# module.net
KiCad netlist of a schematic drawn in EAGLE
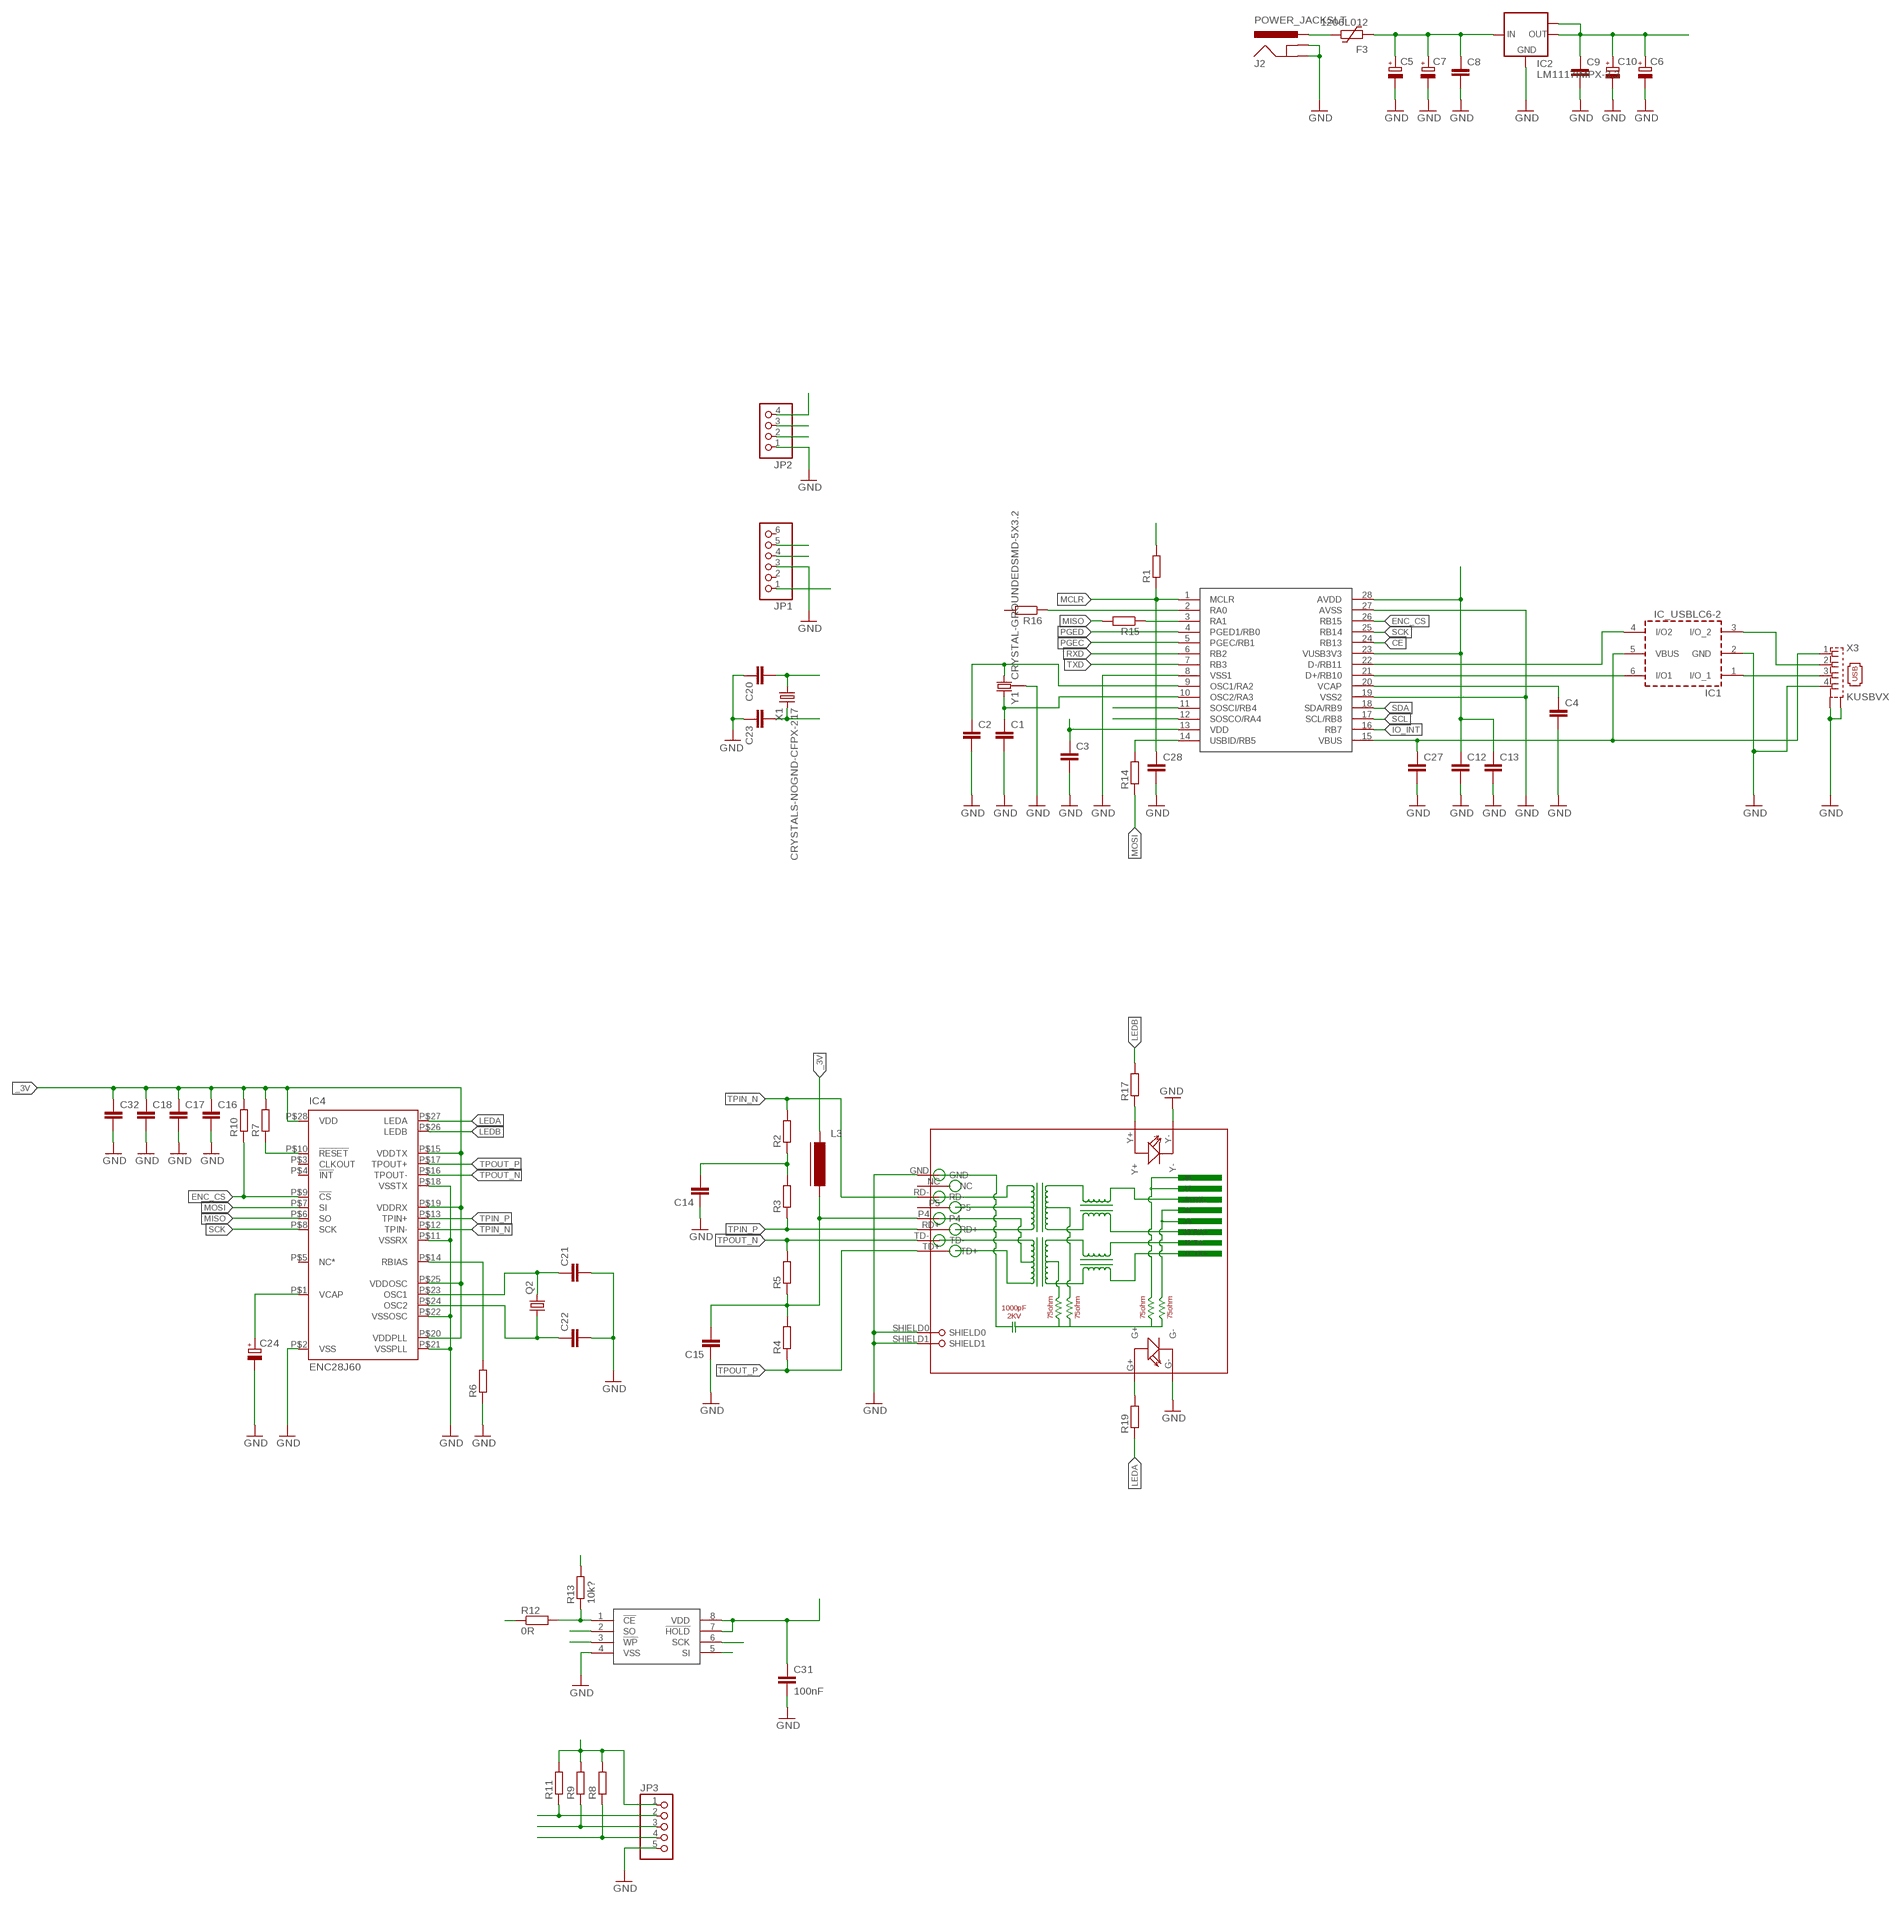
[diagram p0: schematic, sheet 1]

(export (version "E")
  (design (tool "Eeschema 10.0.6"))
  (components
    (comp (ref "C1")
      (value "C-EUC0603")
      (footprint "eagle-import:C0603")
      (libsource (lib "eagle-import") (part "C-EUC0603"))
    )
    (comp (ref "C2")
      (value "C-EUC0603")
      (footprint "eagle-import:C0603")
      (libsource (lib "eagle-import") (part "C-EUC0603"))
    )
    (comp (ref "C3")
      (value "C-EUC0402")
      (footprint "eagle-import:C0402")
      (libsource (lib "eagle-import") (part "C-EUC0402"))
    )
    (comp (ref "C4")
      (value "C-EUC0603")
      (footprint "eagle-import:C0603")
      (libsource (lib "eagle-import") (part "C-EUC0603"))
    )
    (comp (ref "C5")
      (value "CPOL-EUSMCA")
      (footprint "eagle-import:SMC_A")
      (libsource (lib "eagle-import") (part "CPOL-EUSMCA"))
    )
    (comp (ref "C6")
      (value "CPOL-EUSMCA")
      (footprint "eagle-import:SMC_A")
      (libsource (lib "eagle-import") (part "CPOL-EUSMCA"))
    )
    (comp (ref "C7")
      (value "CPOL-EUSMCC")
      (footprint "eagle-import:SMC_C")
      (libsource (lib "eagle-import") (part "CPOL-EUSMCC"))
    )
    (comp (ref "C8")
      (value "C-EUC0603")
      (footprint "eagle-import:C0603")
      (libsource (lib "eagle-import") (part "C-EUC0603"))
    )
    (comp (ref "C9")
      (value "C-EUC0603")
      (footprint "eagle-import:C0603")
      (libsource (lib "eagle-import") (part "C-EUC0603"))
    )
    (comp (ref "C10")
      (value "CPOL-EUSMCB")
      (footprint "eagle-import:SMC_B")
      (libsource (lib "eagle-import") (part "CPOL-EUSMCB"))
    )
    (comp (ref "C12")
      (value "C-EUC0402")
      (footprint "eagle-import:C0402")
      (libsource (lib "eagle-import") (part "C-EUC0402"))
    )
    (comp (ref "C13")
      (value "C-EUC0603")
      (footprint "eagle-import:C0603")
      (libsource (lib "eagle-import") (part "C-EUC0603"))
    )
    (comp (ref "C14")
      (value "C-EUC0603")
      (footprint "eagle-import:C0603")
      (libsource (lib "eagle-import") (part "C-EUC0603"))
    )
    (comp (ref "C15")
      (value "C-EUC0603")
      (footprint "eagle-import:C0603")
      (libsource (lib "eagle-import") (part "C-EUC0603"))
    )
    (comp (ref "C16")
      (value "C-EUC0402")
      (footprint "eagle-import:C0402")
      (libsource (lib "eagle-import") (part "C-EUC0402"))
    )
    (comp (ref "C17")
      (value "C-EUC0603")
      (footprint "eagle-import:C0603")
      (libsource (lib "eagle-import") (part "C-EUC0603"))
    )
    (comp (ref "C18")
      (value "C-EUC0603")
      (footprint "eagle-import:C0603")
      (libsource (lib "eagle-import") (part "C-EUC0603"))
    )
    (comp (ref "C20")
      (value "C-EUC0603")
      (footprint "eagle-import:C0603")
      (libsource (lib "eagle-import") (part "C-EUC0603"))
    )
    (comp (ref "C21")
      (value "C-EUC0603")
      (footprint "eagle-import:C0603")
      (libsource (lib "eagle-import") (part "C-EUC0603"))
    )
    (comp (ref "C22")
      (value "C-EUC0603")
      (footprint "eagle-import:C0603")
      (libsource (lib "eagle-import") (part "C-EUC0603"))
    )
    (comp (ref "C23")
      (value "C-EUC0603")
      (footprint "eagle-import:C0603")
      (libsource (lib "eagle-import") (part "C-EUC0603"))
    )
    (comp (ref "C24")
      (value "CPOL-EUSMCA")
      (footprint "eagle-import:SMC_A")
      (libsource (lib "eagle-import") (part "CPOL-EUSMCA"))
    )
    (comp (ref "C27")
      (value "C-EUC0603")
      (footprint "eagle-import:C0603")
      (libsource (lib "eagle-import") (part "C-EUC0603"))
    )
    (comp (ref "C28")
      (value "C-EUC0603")
      (footprint "eagle-import:C0603")
      (libsource (lib "eagle-import") (part "C-EUC0603"))
    )
    (comp (ref "C31")
      (value "100nF")
      (footprint "eagle-import:C0603")
      (libsource (lib "eagle-import") (part "C-EUC0603"))
    )
    (comp (ref "C32")
      (value "C-EUC0402")
      (footprint "eagle-import:C0402")
      (libsource (lib "eagle-import") (part "C-EUC0402"))
    )
    (comp (ref "F3")
      (value "1206L012")
      (footprint "eagle-import:1206L")
      (fields (field (name "MF") "Littelfuse"))
      (libsource (lib "eagle-import") (part "?1206L012"))
    )
    (comp (ref "IC1")
      (value "IC_USBLC6-2")
      (footprint "eagle-import:SOT-23-6L")
      (libsource (lib "eagle-import") (part "IC_USBLC6-2"))
    )
    (comp (ref "IC2")
      (value "LM1117IMPX-3.3")
      (footprint "eagle-import:SOT223")
      (libsource (lib "eagle-import") (part "LM1117IMPX-3.3"))
    )
    (comp (ref "IC4")
      (value "ENC28J60")
      (footprint "eagle-import:TSSOP28W")
      (libsource (lib "eagle-import") (part "ENC28J60"))
    )
    (comp (ref "J2")
      (value "POWER_JACKSLT")
      (footprint "eagle-import:POWER_JACK_SLOT")
      (libsource (lib "eagle-import") (part "POWER_JACKSLT"))
    )
    (comp (ref "JP1")
      (value "PINHD-1X6")
      (footprint "eagle-import:1X06")
      (libsource (lib "eagle-import") (part "PINHD-1X6"))
    )
    (comp (ref "JP2")
      (value "PINHD-1X4")
      (footprint "eagle-import:1X04")
      (libsource (lib "eagle-import") (part "PINHD-1X4"))
    )
    (comp (ref "JP3")
      (value "PINHD-1X5")
      (footprint "eagle-import:1X05")
      (libsource (lib "eagle-import") (part "PINHD-1X5"))
    )
    (comp (ref "L3")
      (value "FERRITE-0805")
      (footprint "eagle-import:FB805")
      (libsource (lib "eagle-import") (part "FERRITE-0805"))
    )
    (comp (ref "Q2")
      (value "CRYSTALHC49S")
      (footprint "eagle-import:HC49_S")
      (libsource (lib "eagle-import") (part "CRYSTALHC49S"))
    )
    (comp (ref "R1")
      (value "R-EU_R0603")
      (footprint "eagle-import:R0603")
      (libsource (lib "eagle-import") (part "R-EU_R0603"))
    )
    (comp (ref "R2")
      (value "R-EU_R0603")
      (footprint "eagle-import:R0603")
      (libsource (lib "eagle-import") (part "R-EU_R0603"))
    )
    (comp (ref "R3")
      (value "R-EU_R0603")
      (footprint "eagle-import:R0603")
      (libsource (lib "eagle-import") (part "R-EU_R0603"))
    )
    (comp (ref "R4")
      (value "R-EU_R0603")
      (footprint "eagle-import:R0603")
      (libsource (lib "eagle-import") (part "R-EU_R0603"))
    )
    (comp (ref "R5")
      (value "R-EU_R0603")
      (footprint "eagle-import:R0603")
      (libsource (lib "eagle-import") (part "R-EU_R0603"))
    )
    (comp (ref "R6")
      (value "R-EU_R0805")
      (footprint "eagle-import:R0805")
      (libsource (lib "eagle-import") (part "R-EU_R0805"))
    )
    (comp (ref "R7")
      (value "R-EU_R0603")
      (footprint "eagle-import:R0603")
      (libsource (lib "eagle-import") (part "R-EU_R0603"))
    )
    (comp (ref "R8")
      (value "R-EU_R0402")
      (footprint "eagle-import:R0402")
      (libsource (lib "eagle-import") (part "R-EU_R0402"))
    )
    (comp (ref "R9")
      (value "R-EU_R0402")
      (footprint "eagle-import:R0402")
      (libsource (lib "eagle-import") (part "R-EU_R0402"))
    )
    (comp (ref "R10")
      (value "R-EU_R0603")
      (footprint "eagle-import:R0603")
      (libsource (lib "eagle-import") (part "R-EU_R0603"))
    )
    (comp (ref "R11")
      (value "R-EU_R0402")
      (footprint "eagle-import:R0402")
      (libsource (lib "eagle-import") (part "R-EU_R0402"))
    )
    (comp (ref "R12")
      (value "0R")
      (footprint "eagle-import:R0603")
      (libsource (lib "eagle-import") (part "R-EU_R0603"))
    )
    (comp (ref "R13")
      (value "10k?")
      (footprint "eagle-import:R0603")
      (libsource (lib "eagle-import") (part "R-EU_R0603"))
    )
    (comp (ref "R14")
      (value "R-EU_R0603")
      (footprint "eagle-import:R0603")
      (libsource (lib "eagle-import") (part "R-EU_R0603"))
    )
    (comp (ref "R15")
      (value "R-EU_R0603")
      (footprint "eagle-import:R0603")
      (libsource (lib "eagle-import") (part "R-EU_R0603"))
    )
    (comp (ref "R16")
      (value "R-EU_R1206")
      (footprint "eagle-import:R1206")
      (libsource (lib "eagle-import") (part "R-EU_R1206"))
    )
    (comp (ref "R17")
      (value "R-EU_R1206")
      (footprint "eagle-import:R1206")
      (libsource (lib "eagle-import") (part "R-EU_R1206"))
    )
    (comp (ref "R19")
      (value "R-EU_R1206")
      (footprint "eagle-import:R1206")
      (libsource (lib "eagle-import") (part "R-EU_R1206"))
    )
    (comp (ref "RJ1")
      (value "HR911105A")
      (footprint "eagle-import:HR911105A")
      (libsource (lib "eagle-import") (part "HR911105A"))
    )
    (comp (ref "U$1")
      (value "PIC32MX250F128B2")
      (footprint "eagle-import:SSOP28")
      (libsource (lib "eagle-import") (part "PIC32MX250F128B2"))
    )
    (comp (ref "U$2")
      (value "SST25VF016BSO8M")
      (footprint "eagle-import:SO-08M")
      (libsource (lib "eagle-import") (part "SST25VF016BSO8M"))
    )
    (comp (ref "X1")
      (value "CRYSTALS-NOGND-CFPX-217")
      (footprint "eagle-import:3.2X1.5-2-PAD")
      (libsource (lib "eagle-import") (part "CRYSTALS-NOGND-CFPX-217"))
    )
    (comp (ref "X3")
      (value "KUSBVX")
      (footprint "eagle-import:KUSBVX")
      (libsource (lib "eagle-import") (part "KUSBVX"))
    )
    (comp (ref "Y1")
      (value "CRYSTAL-GROUNDEDSMD-5X3.2")
      (footprint "eagle-import:CRYSTAL-SMD-5X3.2-4PAD")
      (libsource (lib "eagle-import") (part "CRYSTAL-GROUNDEDSMD-5X3.2"))
    )
  )
  (nets
    (net (code "1") (name "/SOSCI") (class "Default")
      (node (ref "C20") (pin "2") (pinfunction "2_2") (pintype "passive"))
      (node (ref "U$1") (pin "11") (pinfunction "SOSCI/RB4_11") (pintype "bidirectional"))
      (node (ref "X1") (pin "1") (pinfunction "1_1") (pintype "passive"))
    )
    (net (code "2") (name "/SOSCO") (class "Default")
      (node (ref "C23") (pin "2") (pinfunction "2_2") (pintype "passive"))
      (node (ref "U$1") (pin "12") (pinfunction "SOSCO/RA4_12") (pintype "bidirectional"))
      (node (ref "X1") (pin "2") (pinfunction "2_2") (pintype "passive"))
    )
    (net (code "3") (name "/VBUS") (class "Default")
      (node (ref "C27") (pin "1") (pinfunction "1_1") (pintype "passive"))
      (node (ref "C5") (pin "+") (pinfunction "+_+") (pintype "passive"))
      (node (ref "C7") (pin "+") (pinfunction "+_+") (pintype "passive"))
      (node (ref "C8") (pin "1") (pinfunction "1_1") (pintype "passive"))
      (node (ref "F3") (pin "2") (pinfunction "2_2") (pintype "passive"))
      (node (ref "IC1") (pin "5") (pinfunction "VBUS_5") (pintype "bidirectional"))
      (node (ref "IC2") (pin "3") (pinfunction "IN_3") (pintype "input"))
      (node (ref "U$1") (pin "15") (pinfunction "VBUS_15") (pintype "bidirectional"))
      (node (ref "X3") (pin "1") (pinfunction "1_1") (pintype "passive"))
    )
    (net (code "4") (name "CE") (class "Default")
      (node (ref "R12") (pin "1") (pinfunction "1_1") (pintype "passive"))
      (node (ref "U$1") (pin "24") (pinfunction "RB13_24") (pintype "bidirectional"))
    )
    (net (code "5") (name "ENC_CS") (class "Default")
      (node (ref "IC4") (pin "P$9") (pinfunction "~{CS}_P$9") (pintype "input"))
      (node (ref "R10") (pin "1") (pinfunction "1_1") (pintype "passive"))
      (node (ref "U$1") (pin "26") (pinfunction "RB15_26") (pintype "bidirectional"))
    )
    (net (code "6") (name "GND") (class "Default")
      (node (ref "C1") (pin "2") (pinfunction "2_2") (pintype "passive"))
      (node (ref "C10") (pin "-") (pinfunction "-_-") (pintype "passive"))
      (node (ref "C12") (pin "2") (pinfunction "2_2") (pintype "passive"))
      (node (ref "C13") (pin "2") (pinfunction "2_2") (pintype "passive"))
      (node (ref "C14") (pin "1") (pinfunction "1_1") (pintype "passive"))
      (node (ref "C15") (pin "1") (pinfunction "1_1") (pintype "passive"))
      (node (ref "C16") (pin "2") (pinfunction "2_2") (pintype "passive"))
      (node (ref "C17") (pin "2") (pinfunction "2_2") (pintype "passive"))
      (node (ref "C18") (pin "2") (pinfunction "2_2") (pintype "passive"))
      (node (ref "C2") (pin "2") (pinfunction "2_2") (pintype "passive"))
      (node (ref "C20") (pin "1") (pinfunction "1_1") (pintype "passive"))
      (node (ref "C21") (pin "2") (pinfunction "2_2") (pintype "passive"))
      (node (ref "C22") (pin "2") (pinfunction "2_2") (pintype "passive"))
      (node (ref "C23") (pin "1") (pinfunction "1_1") (pintype "passive"))
      (node (ref "C24") (pin "-") (pinfunction "-_-") (pintype "passive"))
      (node (ref "C27") (pin "2") (pinfunction "2_2") (pintype "passive"))
      (node (ref "C28") (pin "2") (pinfunction "2_2") (pintype "passive"))
      (node (ref "C3") (pin "2") (pinfunction "2_2") (pintype "passive"))
      (node (ref "C31") (pin "2") (pinfunction "2_2") (pintype "passive"))
      (node (ref "C32") (pin "2") (pinfunction "2_2") (pintype "passive"))
      (node (ref "C4") (pin "2") (pinfunction "2_2") (pintype "passive"))
      (node (ref "C5") (pin "-") (pinfunction "-_-") (pintype "passive"))
      (node (ref "C6") (pin "-") (pinfunction "-_-") (pintype "passive"))
      (node (ref "C7") (pin "-") (pinfunction "-_-") (pintype "passive"))
      (node (ref "C8") (pin "2") (pinfunction "2_2") (pintype "passive"))
      (node (ref "C9") (pin "2") (pinfunction "2_2") (pintype "passive"))
      (node (ref "IC1") (pin "2") (pinfunction "GND_2") (pintype "bidirectional"))
      (node (ref "IC2") (pin "1") (pinfunction "GND_1") (pintype "input"))
      (node (ref "IC4") (pin "P$11") (pinfunction "VSSRX_P$11") (pintype "input"))
      (node (ref "IC4") (pin "P$18") (pinfunction "VSSTX_P$18") (pintype "input"))
      (node (ref "IC4") (pin "P$2") (pinfunction "VSS_P$2") (pintype "input"))
      (node (ref "IC4") (pin "P$21") (pinfunction "VSSPLL_P$21") (pintype "input"))
      (node (ref "IC4") (pin "P$22") (pinfunction "VSSOSC_P$22") (pintype "input"))
      (node (ref "J2") (pin "GND@1") (pinfunction "GNDBREAK_GND@1") (pintype "bidirectional"))
      (node (ref "J2") (pin "GND@2") (pinfunction "GND_GND@2") (pintype "bidirectional"))
      (node (ref "JP1") (pin "3") (pinfunction "3_3") (pintype "passive"))
      (node (ref "JP2") (pin "1") (pinfunction "1_1") (pintype "passive"))
      (node (ref "JP3") (pin "5") (pinfunction "5_5") (pintype "passive"))
      (node (ref "R6") (pin "1") (pinfunction "1_1") (pintype "passive"))
      (node (ref "RJ1") (pin "G-") (pinfunction "G-_G-") (pintype "bidirectional"))
      (node (ref "RJ1") (pin "GND") (pinfunction "GND_GND") (pintype "bidirectional"))
      (node (ref "RJ1") (pin "SHIELD0") (pinfunction "SHIELD0_SHIELD0") (pintype "bidirectional"))
      (node (ref "RJ1") (pin "SHIELD1") (pinfunction "SHIELD1_SHIELD1") (pintype "bidirectional"))
      (node (ref "RJ1") (pin "Y-") (pinfunction "Y-_Y-") (pintype "bidirectional"))
      (node (ref "U$1") (pin "19") (pinfunction "VSS2_19") (pintype "bidirectional"))
      (node (ref "U$1") (pin "27") (pinfunction "AVSS_27") (pintype "bidirectional"))
      (node (ref "U$1") (pin "8") (pinfunction "VSS1_8") (pintype "bidirectional"))
      (node (ref "U$2") (pin "4") (pinfunction "VSS_4") (pintype "bidirectional"))
      (node (ref "X3") (pin "4") (pinfunction "4_4") (pintype "passive"))
      (node (ref "X3") (pin "M1") (pinfunction "S1_M1") (pintype "passive"))
      (node (ref "X3") (pin "M2") (pinfunction "S2_M2") (pintype "passive"))
      (node (ref "Y1") (pin "2") (pinfunction "3_2") (pintype "passive"))
      (node (ref "Y1") (pin "4") (pinfunction "3_4") (pintype "passive"))
    )
    (net (code "7") (name "IO_INT") (class "Default")
      (node (ref "JP3") (pin "4") (pinfunction "4_4") (pintype "passive"))
      (node (ref "R8") (pin "1") (pinfunction "1_1") (pintype "passive"))
      (node (ref "U$1") (pin "16") (pinfunction "RB7_16") (pintype "bidirectional"))
    )
    (net (code "8") (name "LEDA") (class "Default")
      (node (ref "IC4") (pin "P$27") (pinfunction "LEDA_P$27") (pintype "output"))
      (node (ref "R19") (pin "1") (pinfunction "1_1") (pintype "passive"))
    )
    (net (code "9") (name "LEDB") (class "Default")
      (node (ref "IC4") (pin "P$26") (pinfunction "LEDB_P$26") (pintype "output"))
      (node (ref "R17") (pin "2") (pinfunction "2_2") (pintype "passive"))
    )
    (net (code "10") (name "MCLR") (class "Default")
      (node (ref "C28") (pin "1") (pinfunction "1_1") (pintype "passive"))
      (node (ref "JP1") (pin "1") (pinfunction "1_1") (pintype "passive"))
      (node (ref "R1") (pin "1") (pinfunction "1_1") (pintype "passive"))
      (node (ref "U$1") (pin "1") (pinfunction "MCLR_1") (pintype "bidirectional"))
    )
    (net (code "11") (name "MISO") (class "Default")
      (node (ref "IC4") (pin "P$6") (pinfunction "SO_P$6") (pintype "output"))
      (node (ref "R15") (pin "2") (pinfunction "2_2") (pintype "passive"))
      (node (ref "U$2") (pin "2") (pinfunction "SO_2") (pintype "bidirectional"))
    )
    (net (code "12") (name "MOSI") (class "Default")
      (node (ref "IC4") (pin "P$7") (pinfunction "SI_P$7") (pintype "input"))
      (node (ref "R14") (pin "1") (pinfunction "1_1") (pintype "passive"))
      (node (ref "U$2") (pin "5") (pinfunction "SI_5") (pintype "bidirectional"))
    )
    (net (code "13") (name "Net-(C14-Pad2)") (class "Default")
      (node (ref "C14") (pin "2") (pinfunction "2_2") (pintype "passive"))
      (node (ref "R2") (pin "1") (pinfunction "1_1") (pintype "passive"))
      (node (ref "R3") (pin "2") (pinfunction "2_2") (pintype "passive"))
    )
    (net (code "14") (name "Net-(C15-Pad2)") (class "Default")
      (node (ref "C15") (pin "2") (pinfunction "2_2") (pintype "passive"))
      (node (ref "L3") (pin "2") (pinfunction "2_2") (pintype "passive"))
      (node (ref "R4") (pin "2") (pinfunction "2_2") (pintype "passive"))
      (node (ref "R5") (pin "1") (pinfunction "1_1") (pintype "passive"))
      (node (ref "RJ1") (pin "P4") (pinfunction "P4_P4") (pintype "bidirectional"))
    )
    (net (code "15") (name "Net-(F3-Pad1)") (class "Default")
      (node (ref "F3") (pin "1") (pinfunction "1_1") (pintype "passive"))
      (node (ref "J2") (pin "PWR") (pinfunction "PWR_PWR") (pintype "bidirectional"))
    )
    (net (code "16") (name "Net-(IC1-I{slash}O1)") (class "Default")
      (node (ref "IC1") (pin "6") (pinfunction "I/O1_6") (pintype "bidirectional"))
      (node (ref "U$1") (pin "21") (pinfunction "D+/RB10_21") (pintype "bidirectional"))
    )
    (net (code "17") (name "Net-(IC1-I{slash}O2)") (class "Default")
      (node (ref "IC1") (pin "4") (pinfunction "I/O2_4") (pintype "bidirectional"))
      (node (ref "U$1") (pin "22") (pinfunction "D-/RB11_22") (pintype "bidirectional"))
    )
    (net (code "18") (name "Net-(IC1-I{slash}O_1)") (class "Default")
      (node (ref "IC1") (pin "1") (pinfunction "I/O_1_1") (pintype "bidirectional"))
      (node (ref "X3") (pin "3") (pinfunction "3_3") (pintype "passive"))
    )
    (net (code "19") (name "Net-(IC1-I{slash}O_2)") (class "Default")
      (node (ref "IC1") (pin "3") (pinfunction "I/O_2_3") (pintype "bidirectional"))
      (node (ref "X3") (pin "2") (pinfunction "2_2") (pintype "passive"))
    )
    (net (code "20") (name "Net-(IC4-OSC1)") (class "Default")
      (node (ref "C21") (pin "1") (pinfunction "1_1") (pintype "passive"))
      (node (ref "IC4") (pin "P$23") (pinfunction "OSC1_P$23") (pintype "input"))
      (node (ref "Q2") (pin "2") (pinfunction "2_2") (pintype "passive"))
    )
    (net (code "21") (name "Net-(IC4-OSC2)") (class "Default")
      (node (ref "C22") (pin "1") (pinfunction "1_1") (pintype "passive"))
      (node (ref "IC4") (pin "P$24") (pinfunction "OSC2_P$24") (pintype "output"))
      (node (ref "Q2") (pin "1") (pinfunction "1_1") (pintype "passive"))
    )
    (net (code "22") (name "Net-(IC4-RBIAS)") (class "Default")
      (node (ref "IC4") (pin "P$14") (pinfunction "RBIAS_P$14") (pintype "input"))
      (node (ref "R6") (pin "2") (pinfunction "2_2") (pintype "passive"))
    )
    (net (code "23") (name "Net-(IC4-VCAP)") (class "Default")
      (node (ref "C24") (pin "+") (pinfunction "+_+") (pintype "passive"))
      (node (ref "IC4") (pin "P$1") (pinfunction "VCAP_P$1") (pintype "input"))
    )
    (net (code "24") (name "Net-(IC4-~{RESET})") (class "Default")
      (node (ref "IC4") (pin "P$10") (pinfunction "~{RESET}_P$10") (pintype "input"))
      (node (ref "R7") (pin "1") (pinfunction "1_1") (pintype "passive"))
    )
    (net (code "25") (name "Net-(R17-Pad1)") (class "Default")
      (node (ref "R17") (pin "1") (pinfunction "1_1") (pintype "passive"))
      (node (ref "RJ1") (pin "Y+") (pinfunction "Y+_Y+") (pintype "bidirectional"))
    )
    (net (code "26") (name "Net-(R19-Pad2)") (class "Default")
      (node (ref "R19") (pin "2") (pinfunction "2_2") (pintype "passive"))
      (node (ref "RJ1") (pin "G+") (pinfunction "G+_G+") (pintype "bidirectional"))
    )
    (net (code "27") (name "Net-(U$1-OSC1{slash}RA2)") (class "Default")
      (node (ref "C2") (pin "1") (pinfunction "1_1") (pintype "passive"))
      (node (ref "U$1") (pin "9") (pinfunction "OSC1/RA2_9") (pintype "bidirectional"))
      (node (ref "Y1") (pin "1") (pinfunction "2_1") (pintype "passive"))
    )
    (net (code "28") (name "Net-(U$1-OSC2{slash}RA3)") (class "Default")
      (node (ref "C1") (pin "1") (pinfunction "1_1") (pintype "passive"))
      (node (ref "U$1") (pin "10") (pinfunction "OSC2/RA3_10") (pintype "bidirectional"))
      (node (ref "Y1") (pin "3") (pinfunction "1_3") (pintype "passive"))
    )
    (net (code "29") (name "Net-(U$1-RA0)") (class "Default")
      (node (ref "R16") (pin "1") (pinfunction "1_1") (pintype "passive"))
      (node (ref "U$1") (pin "2") (pinfunction "RA0_2") (pintype "bidirectional"))
    )
    (net (code "30") (name "Net-(U$1-RA1)") (class "Default")
      (node (ref "R15") (pin "1") (pinfunction "1_1") (pintype "passive"))
      (node (ref "U$1") (pin "3") (pinfunction "RA1_3") (pintype "bidirectional"))
    )
    (net (code "31") (name "Net-(U$1-USBID{slash}RB5)") (class "Default")
      (node (ref "R14") (pin "2") (pinfunction "2_2") (pintype "passive"))
      (node (ref "U$1") (pin "14") (pinfunction "USBID/RB5_14") (pintype "bidirectional"))
    )
    (net (code "32") (name "Net-(U$1-VCAP)") (class "Default")
      (node (ref "C4") (pin "1") (pinfunction "1_1") (pintype "passive"))
      (node (ref "U$1") (pin "20") (pinfunction "VCAP_20") (pintype "bidirectional"))
    )
    (net (code "33") (name "Net-(U$2-~{CE})") (class "Default")
      (node (ref "R12") (pin "2") (pinfunction "2_2") (pintype "passive"))
      (node (ref "R13") (pin "1") (pinfunction "1_1") (pintype "passive"))
      (node (ref "U$2") (pin "1") (pinfunction "~{CE}_1") (pintype "bidirectional"))
    )
    (net (code "34") (name "PGEC") (class "Default")
      (node (ref "JP1") (pin "5") (pinfunction "5_5") (pintype "passive"))
      (node (ref "U$1") (pin "5") (pinfunction "PGEC/RB1_5") (pintype "bidirectional"))
    )
    (net (code "35") (name "PGED") (class "Default")
      (node (ref "JP1") (pin "4") (pinfunction "4_4") (pintype "passive"))
      (node (ref "U$1") (pin "4") (pinfunction "PGED1/RB0_4") (pintype "bidirectional"))
    )
    (net (code "36") (name "RXD") (class "Default")
      (node (ref "JP2") (pin "3") (pinfunction "3_3") (pintype "passive"))
      (node (ref "U$1") (pin "6") (pinfunction "RB2_6") (pintype "bidirectional"))
    )
    (net (code "37") (name "SCK") (class "Default")
      (node (ref "IC4") (pin "P$8") (pinfunction "SCK_P$8") (pintype "input"))
      (node (ref "U$1") (pin "25") (pinfunction "RB14_25") (pintype "bidirectional"))
      (node (ref "U$2") (pin "6") (pinfunction "SCK_6") (pintype "bidirectional"))
    )
    (net (code "38") (name "SCL") (class "Default")
      (node (ref "JP3") (pin "3") (pinfunction "3_3") (pintype "passive"))
      (node (ref "R9") (pin "1") (pinfunction "1_1") (pintype "passive"))
      (node (ref "U$1") (pin "17") (pinfunction "SCL/RB8_17") (pintype "bidirectional"))
    )
    (net (code "39") (name "SDA") (class "Default")
      (node (ref "JP3") (pin "2") (pinfunction "2_2") (pintype "passive"))
      (node (ref "R11") (pin "1") (pinfunction "1_1") (pintype "passive"))
      (node (ref "U$1") (pin "18") (pinfunction "SDA/RB9_18") (pintype "bidirectional"))
    )
    (net (code "40") (name "TPIN_N") (class "Default")
      (node (ref "IC4") (pin "P$12") (pinfunction "TPIN-_P$12") (pintype "input"))
      (node (ref "R2") (pin "2") (pinfunction "2_2") (pintype "passive"))
      (node (ref "RJ1") (pin "RD-") (pinfunction "RD-_RD-") (pintype "bidirectional"))
    )
    (net (code "41") (name "TPIN_P") (class "Default")
      (node (ref "IC4") (pin "P$13") (pinfunction "TPIN+_P$13") (pintype "input"))
      (node (ref "R3") (pin "1") (pinfunction "1_1") (pintype "passive"))
      (node (ref "RJ1") (pin "RD+") (pinfunction "RD+_RD+") (pintype "bidirectional"))
    )
    (net (code "42") (name "TPOUT_N") (class "Default")
      (node (ref "IC4") (pin "P$16") (pinfunction "TPOUT-_P$16") (pintype "output"))
      (node (ref "R5") (pin "2") (pinfunction "2_2") (pintype "passive"))
      (node (ref "RJ1") (pin "TD-") (pinfunction "TD-_TD-") (pintype "bidirectional"))
    )
    (net (code "43") (name "TPOUT_P") (class "Default")
      (node (ref "IC4") (pin "P$17") (pinfunction "TPOUT+_P$17") (pintype "output"))
      (node (ref "R4") (pin "1") (pinfunction "1_1") (pintype "passive"))
      (node (ref "RJ1") (pin "TD+") (pinfunction "TD+_TD+") (pintype "bidirectional"))
    )
    (net (code "44") (name "TXD") (class "Default")
      (node (ref "JP2") (pin "2") (pinfunction "2_2") (pintype "passive"))
      (node (ref "U$1") (pin "7") (pinfunction "RB3_7") (pintype "bidirectional"))
    )
    (net (code "45") (name "_3V") (class "Default")
      (node (ref "C10") (pin "+") (pinfunction "+_+") (pintype "passive"))
      (node (ref "C12") (pin "1") (pinfunction "1_1") (pintype "passive"))
      (node (ref "C13") (pin "1") (pinfunction "1_1") (pintype "passive"))
      (node (ref "C16") (pin "1") (pinfunction "1_1") (pintype "passive"))
      (node (ref "C17") (pin "1") (pinfunction "1_1") (pintype "passive"))
      (node (ref "C18") (pin "1") (pinfunction "1_1") (pintype "passive"))
      (node (ref "C3") (pin "1") (pinfunction "1_1") (pintype "passive"))
      (node (ref "C31") (pin "1") (pinfunction "1_1") (pintype "passive"))
      (node (ref "C32") (pin "1") (pinfunction "1_1") (pintype "passive"))
      (node (ref "C6") (pin "+") (pinfunction "+_+") (pintype "passive"))
      (node (ref "C9") (pin "1") (pinfunction "1_1") (pintype "passive"))
      (node (ref "IC2") (pin "2") (pinfunction "OUT_2") (pintype "passive"))
      (node (ref "IC2") (pin "TAB") (pinfunction "OUT1_TAB") (pintype "passive"))
      (node (ref "IC4") (pin "P$15") (pinfunction "VDDTX_P$15") (pintype "input"))
      (node (ref "IC4") (pin "P$19") (pinfunction "VDDRX_P$19") (pintype "input"))
      (node (ref "IC4") (pin "P$20") (pinfunction "VDDPLL_P$20") (pintype "input"))
      (node (ref "IC4") (pin "P$25") (pinfunction "VDDOSC_P$25") (pintype "input"))
      (node (ref "IC4") (pin "P$28") (pinfunction "VDD_P$28") (pintype "input"))
      (node (ref "JP2") (pin "4") (pinfunction "4_4") (pintype "passive"))
      (node (ref "JP3") (pin "1") (pinfunction "1_1") (pintype "passive"))
      (node (ref "L3") (pin "1") (pinfunction "1_1") (pintype "passive"))
      (node (ref "R1") (pin "2") (pinfunction "2_2") (pintype "passive"))
      (node (ref "R10") (pin "2") (pinfunction "2_2") (pintype "passive"))
      (node (ref "R11") (pin "2") (pinfunction "2_2") (pintype "passive"))
      (node (ref "R13") (pin "2") (pinfunction "2_2") (pintype "passive"))
      (node (ref "R7") (pin "2") (pinfunction "2_2") (pintype "passive"))
      (node (ref "R8") (pin "2") (pinfunction "2_2") (pintype "passive"))
      (node (ref "R9") (pin "2") (pinfunction "2_2") (pintype "passive"))
      (node (ref "U$1") (pin "13") (pinfunction "VDD_13") (pintype "bidirectional"))
      (node (ref "U$1") (pin "23") (pinfunction "VUSB3V3_23") (pintype "bidirectional"))
      (node (ref "U$1") (pin "28") (pinfunction "AVDD_28") (pintype "bidirectional"))
      (node (ref "U$2") (pin "3") (pinfunction "~{WP}_3") (pintype "bidirectional"))
      (node (ref "U$2") (pin "7") (pinfunction "~{HOLD}_7") (pintype "bidirectional"))
      (node (ref "U$2") (pin "8") (pinfunction "VDD_8") (pintype "bidirectional"))
    )
    (net (code "46") (name "unconnected-(IC4-CLKOUT-PadP$3)") (class "Default")
      (node (ref "IC4") (pin "P$3") (pinfunction "CLKOUT_P$3") (pintype "output"))
    )
    (net (code "47") (name "unconnected-(IC4-NC*-PadP$5)") (class "Default")
      (node (ref "IC4") (pin "P$5") (pinfunction "NC*_P$5") (pintype "output"))
    )
    (net (code "48") (name "unconnected-(IC4-~{INT}-PadP$4)") (class "Default")
      (node (ref "IC4") (pin "P$4") (pinfunction "~{INT}_P$4") (pintype "output"))
    )
    (net (code "49") (name "unconnected-(JP1-Pad2)") (class "Default")
      (node (ref "JP1") (pin "2") (pinfunction "2_2") (pintype "passive"))
    )
    (net (code "50") (name "unconnected-(JP1-Pad6)") (class "Default")
      (node (ref "JP1") (pin "6") (pinfunction "6_6") (pintype "passive"))
    )
    (net (code "51") (name "unconnected-(R16-Pad2)") (class "Default")
      (node (ref "R16") (pin "2") (pinfunction "2_2") (pintype "passive"))
    )
    (net (code "52") (name "unconnected-(RJ1-PadNC)") (class "Default")
      (node (ref "RJ1") (pin "NC") (pinfunction "NC_NC") (pintype "bidirectional"))
    )
    (net (code "53") (name "unconnected-(RJ1-PadP5)") (class "Default")
      (node (ref "RJ1") (pin "P5") (pinfunction "P5_P5") (pintype "bidirectional"))
    )
  )
)
